# Assignment1BMM-Schematic-Ayah_copy.net
KiCad netlist of a schematic drawn in EAGLE
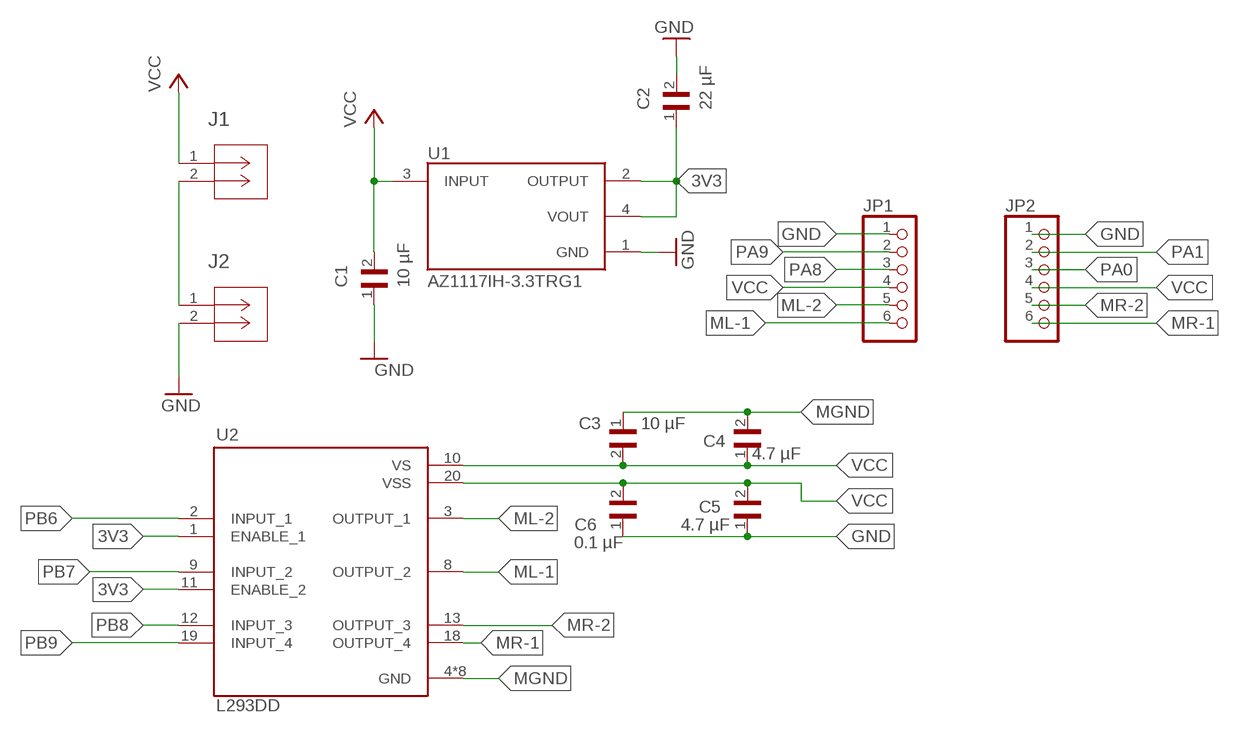
[diagram p0: schematic, sheet 1]

(export (version "E")
  (design (tool "Eeschema 10.0.6"))
  (components
    (comp (ref "C1")
      (value "10 µF")
      (footprint "eagle-import:CAPC2012X135N")
      (fields (field (name "MF") "Murata") (field (name "MP") "GRM21BR61C106KE15L"))
      (libsource (lib "eagle-import") (part "GRM21BR61C106KE15L"))
    )
    (comp (ref "C2")
      (value "22 µF")
      (footprint "eagle-import:CAPC2012X145N")
      (fields (field (name "MF") "Murata") (field (name "MP") "GRM21BR61C226ME44L"))
      (libsource (lib "eagle-import") (part "GRM21BR61C226ME44L"))
    )
    (comp (ref "C3")
      (value "10 µF")
      (footprint "eagle-import:CAPC2012X135N")
      (fields (field (name "MF") "Murata") (field (name "MP") "GRM21BR61C106KE15L"))
      (libsource (lib "eagle-import") (part "GRM21BR61C106KE15L"))
    )
    (comp (ref "C4")
      (value "4.7 µF")
      (footprint "eagle-import:CAPC2012X140N")
      (fields
        (field (name "DIGIKEY_PART_NUMBER") "490-14466-2-ND")
        (field (name "MF") "Murata Electronics")
        (field (name "MP") "GRM21BR71C475KE51L")
      )
      (libsource (lib "eagle-import") (part "GRM21BR71C475KE51L"))
    )
    (comp (ref "C5")
      (value "4.7 µF")
      (footprint "eagle-import:CAPC2012X140N")
      (fields
        (field (name "DIGIKEY_PART_NUMBER") "490-14466-2-ND")
        (field (name "MF") "Murata Electronics")
        (field (name "MP") "GRM21BR71C475KE51L")
      )
      (libsource (lib "eagle-import") (part "GRM21BR71C475KE51L"))
    )
    (comp (ref "C6")
      (value "0.1 µF")
      (footprint "eagle-import:CAPC2012X140N")
      (fields (field (name "MF") "Murata") (field (name "MP") "GCM21BR72A104KA37K"))
      (libsource (lib "eagle-import") (part "GCM21BR72A104KA37K"))
    )
    (comp (ref "J1")
      (value "B2B-PH-K-S")
      (footprint "eagle-import:CONN2_B2B-PH-K-S_JST")
      (fields (field (name "COPYRIGHT") "Copyright (C) 2023 Ultra Librarian. All rights reserved."))
      (libsource (lib "eagle-import") (part "B2B-PH-K-S"))
    )
    (comp (ref "J2")
      (value "B2B-PH-K-S")
      (footprint "eagle-import:CONN2_B2B-PH-K-S_JST")
      (fields (field (name "COPYRIGHT") "Copyright (C) 2023 Ultra Librarian. All rights reserved."))
      (libsource (lib "eagle-import") (part "B2B-PH-K-S"))
    )
    (comp (ref "JP1")
      (value "PINHD-1X6")
      (footprint "eagle-import:1X06")
      (libsource (lib "eagle-import") (part "PINHD-1X6"))
    )
    (comp (ref "JP2")
      (value "PINHD-1X6")
      (footprint "eagle-import:1X06")
      (libsource (lib "eagle-import") (part "PINHD-1X6"))
    )
    (comp (ref "U1")
      (value "AZ1117IH-3.3TRG1")
      (footprint "eagle-import:SOT230P700X185-4N")
      (fields (field (name "MF") "Diodes Inc."))
      (libsource (lib "eagle-import") (part "AZ1117IH-3.3TRG1"))
    )
    (comp (ref "U2")
      (value "L293DD")
      (footprint "eagle-import:SOIC127P1032X265-20N")
      (fields (field (name "DIGIKEY_PART_NUMBER") "497-1390-5-ND") (field (name "MF") "STMicroelectronics"))
      (libsource (lib "eagle-import") (part "L293DD"))
    )
  )
  (nets
    (net (code "1") (name "3V3") (class "Default")
      (node (ref "C2") (pin "1") (pinfunction "1_1") (pintype "passive"))
      (node (ref "U1") (pin "2") (pinfunction "OUTPUT_2") (pintype "output"))
      (node (ref "U1") (pin "4") (pinfunction "VOUT_4") (pintype "output"))
      (node (ref "U2") (pin "1") (pinfunction "ENABLE_1_1") (pintype "input"))
      (node (ref "U2") (pin "11") (pinfunction "ENABLE_2_11") (pintype "input"))
    )
    (net (code "2") (name "GND") (class "Default")
      (node (ref "C1") (pin "1") (pinfunction "1_1") (pintype "passive"))
      (node (ref "C2") (pin "2") (pinfunction "2_2") (pintype "passive"))
      (node (ref "C5") (pin "1") (pinfunction "1_1") (pintype "passive"))
      (node (ref "C6") (pin "1") (pinfunction "1_1") (pintype "passive"))
      (node (ref "J2") (pin "2") (pinfunction "2_2") (pintype "passive"))
      (node (ref "JP1") (pin "1") (pinfunction "1_1") (pintype "passive"))
      (node (ref "JP2") (pin "1") (pinfunction "1_1") (pintype "passive"))
      (node (ref "U1") (pin "1") (pinfunction "GND_1") (pintype "power_in"))
    )
    (net (code "3") (name "MGND") (class "Default")
      (node (ref "C3") (pin "1") (pinfunction "1_1") (pintype "passive"))
      (node (ref "C4") (pin "2") (pinfunction "2_2") (pintype "passive"))
      (node (ref "U2") (pin "14") (pinfunction "GND_14") (pintype "power_in"))
      (node (ref "U2") (pin "15") (pinfunction "GND_15") (pintype "power_in"))
      (node (ref "U2") (pin "16") (pinfunction "GND_16") (pintype "power_in"))
      (node (ref "U2") (pin "17") (pinfunction "GND_17") (pintype "power_in"))
      (node (ref "U2") (pin "4") (pinfunction "GND_4") (pintype "power_in"))
      (node (ref "U2") (pin "5") (pinfunction "GND_5") (pintype "power_in"))
      (node (ref "U2") (pin "6") (pinfunction "GND_6") (pintype "power_in"))
      (node (ref "U2") (pin "7") (pinfunction "GND_7") (pintype "power_in"))
    )
    (net (code "4") (name "ML-1") (class "Default")
      (node (ref "JP1") (pin "6") (pinfunction "6_6") (pintype "passive"))
      (node (ref "U2") (pin "8") (pinfunction "OUTPUT_2_8") (pintype "output"))
    )
    (net (code "5") (name "ML-2") (class "Default")
      (node (ref "JP1") (pin "5") (pinfunction "5_5") (pintype "passive"))
      (node (ref "U2") (pin "3") (pinfunction "OUTPUT_1_3") (pintype "output"))
    )
    (net (code "6") (name "MR-1") (class "Default")
      (node (ref "JP2") (pin "6") (pinfunction "6_6") (pintype "passive"))
      (node (ref "U2") (pin "18") (pinfunction "OUTPUT_4_18") (pintype "output"))
    )
    (net (code "7") (name "MR-2") (class "Default")
      (node (ref "JP2") (pin "5") (pinfunction "5_5") (pintype "passive"))
      (node (ref "U2") (pin "13") (pinfunction "OUTPUT_3_13") (pintype "output"))
    )
    (net (code "8") (name "Net-(J1-Pad2)") (class "Default")
      (node (ref "J1") (pin "2") (pinfunction "2_2") (pintype "passive"))
      (node (ref "J2") (pin "1") (pinfunction "1_1") (pintype "passive"))
    )
    (net (code "9") (name "PA0") (class "Default")
      (node (ref "JP2") (pin "3") (pinfunction "3_3") (pintype "passive"))
    )
    (net (code "10") (name "PA1") (class "Default")
      (node (ref "JP2") (pin "2") (pinfunction "2_2") (pintype "passive"))
    )
    (net (code "11") (name "PA8") (class "Default")
      (node (ref "JP1") (pin "3") (pinfunction "3_3") (pintype "passive"))
    )
    (net (code "12") (name "PA9") (class "Default")
      (node (ref "JP1") (pin "2") (pinfunction "2_2") (pintype "passive"))
    )
    (net (code "13") (name "PB6") (class "Default")
      (node (ref "U2") (pin "2") (pinfunction "INPUT_1_2") (pintype "input"))
    )
    (net (code "14") (name "PB7") (class "Default")
      (node (ref "U2") (pin "9") (pinfunction "INPUT_2_9") (pintype "input"))
    )
    (net (code "15") (name "PB8") (class "Default")
      (node (ref "U2") (pin "12") (pinfunction "INPUT_3_12") (pintype "input"))
    )
    (net (code "16") (name "PB9") (class "Default")
      (node (ref "U2") (pin "19") (pinfunction "INPUT_4_19") (pintype "input"))
    )
    (net (code "17") (name "VCC") (class "Default")
      (node (ref "C1") (pin "2") (pinfunction "2_2") (pintype "passive"))
      (node (ref "C3") (pin "2") (pinfunction "2_2") (pintype "passive"))
      (node (ref "C4") (pin "1") (pinfunction "1_1") (pintype "passive"))
      (node (ref "C5") (pin "2") (pinfunction "2_2") (pintype "passive"))
      (node (ref "C6") (pin "2") (pinfunction "2_2") (pintype "passive"))
      (node (ref "J1") (pin "1") (pinfunction "1_1") (pintype "passive"))
      (node (ref "JP1") (pin "4") (pinfunction "4_4") (pintype "passive"))
      (node (ref "JP2") (pin "4") (pinfunction "4_4") (pintype "passive"))
      (node (ref "U1") (pin "3") (pinfunction "INPUT_3") (pintype "input"))
      (node (ref "U2") (pin "10") (pinfunction "VS_10") (pintype "power_in"))
      (node (ref "U2") (pin "20") (pinfunction "VSS_20") (pintype "power_in"))
    )
  )
)
